# Power.net
KiCad netlist of a schematic drawn in Altium Designer
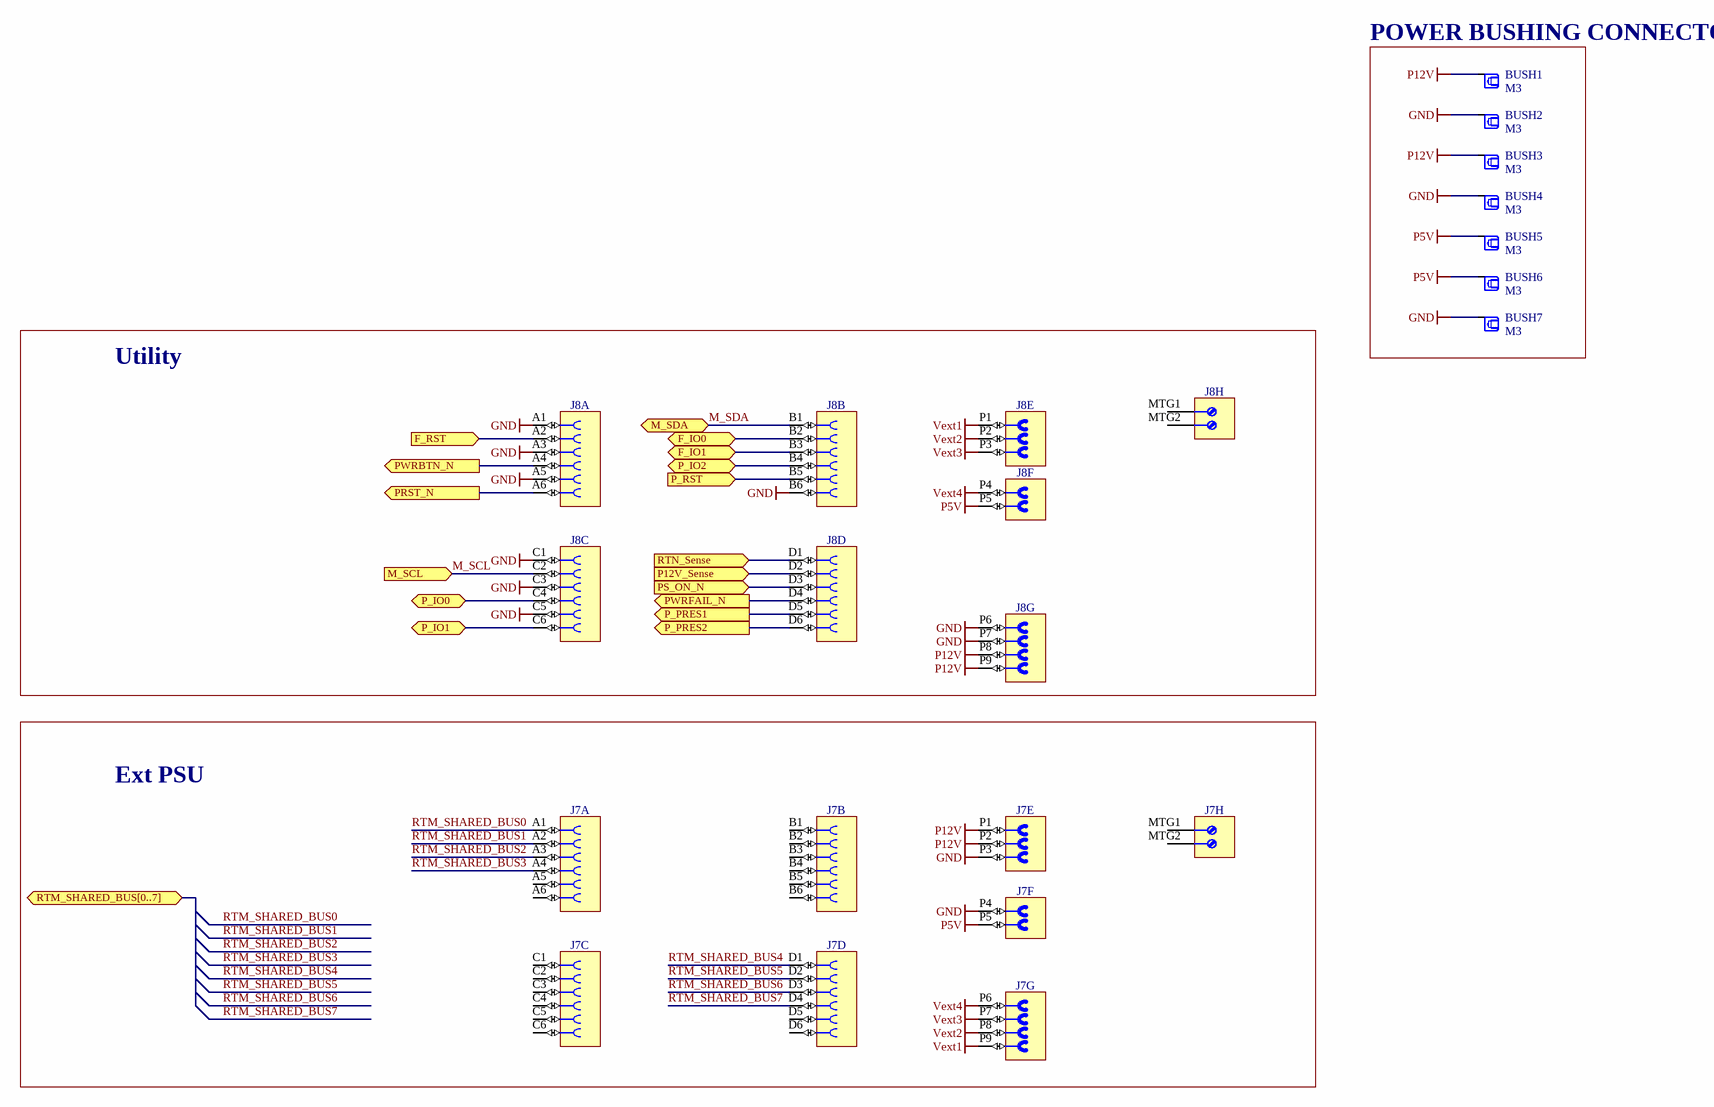
[diagram p0: Power.SchDoc]

(export (version "E")
  (design (tool "Eeschema 10.0.6"))
  (components
    (comp (ref "BUSH1")
      (value "M3")
      (footprint "WURTH_7461057")
      (description "Bush")
      (fields
        (field (name "PART NUMBER") "WURTH_7461057")
        (field (name "MANUFACTURER") "WURTH")
        (field (name "AUTHOR") "CERN DEM JLC")
      )
      (libsource (lib "Eletro-mechanical") (part "Bush"))
    )
    (comp (ref "BUSH2")
      (value "M3")
      (footprint "WURTH_7461057")
      (description "Bush")
      (fields
        (field (name "PART NUMBER") "WURTH_7461057")
        (field (name "MANUFACTURER") "WURTH")
        (field (name "AUTHOR") "CERN DEM JLC")
      )
      (libsource (lib "Eletro-mechanical") (part "Bush"))
    )
    (comp (ref "BUSH3")
      (value "M3")
      (footprint "WURTH_7461057")
      (description "Bush")
      (fields
        (field (name "PART NUMBER") "WURTH_7461057")
        (field (name "MANUFACTURER") "WURTH")
        (field (name "AUTHOR") "CERN DEM JLC")
      )
      (libsource (lib "Eletro-mechanical") (part "Bush"))
    )
    (comp (ref "BUSH4")
      (value "M3")
      (footprint "WURTH_7461057")
      (description "Bush")
      (fields
        (field (name "PART NUMBER") "WURTH_7461057")
        (field (name "MANUFACTURER") "WURTH")
        (field (name "AUTHOR") "CERN DEM JLC")
      )
      (libsource (lib "Eletro-mechanical") (part "Bush"))
    )
    (comp (ref "BUSH5")
      (value "M3")
      (footprint "WURTH_7461057")
      (description "Bush")
      (fields
        (field (name "PART NUMBER") "WURTH_7461057")
        (field (name "MANUFACTURER") "WURTH")
        (field (name "AUTHOR") "CERN DEM JLC")
      )
      (libsource (lib "Eletro-mechanical") (part "Bush"))
    )
    (comp (ref "BUSH6")
      (value "M3")
      (footprint "WURTH_7461057")
      (description "Bush")
      (fields
        (field (name "PART NUMBER") "WURTH_7461057")
        (field (name "MANUFACTURER") "WURTH")
        (field (name "AUTHOR") "CERN DEM JLC")
      )
      (libsource (lib "Eletro-mechanical") (part "Bush"))
    )
    (comp (ref "BUSH7")
      (value "M3")
      (footprint "WURTH_7461057")
      (description "Bush")
      (fields
        (field (name "PART NUMBER") "WURTH_7461057")
        (field (name "MANUFACTURER") "WURTH")
        (field (name "AUTHOR") "CERN DEM JLC")
      )
      (libsource (lib "Eletro-mechanical") (part "Bush"))
    )
    (comp (ref "J7")
      (value "PwrBlade")
      (footprint "AMPHENOL_51940-650")
      (description "Thru-Hole, Lead 3.43mm, PowerBlade Vertical Power Connector 3ACP 2P 24S 4DCP Contacts")
      (fields
        (field (name "PART NUMBER") "AMPHENOL_51940-650")
        (field (name "MANUFACTURER") "AMPHENOL")
        (field (name "AUTHOR") "CERN DEM HF")
      )
      (libsource (lib "Connectors") (part "AMPHENOL_51940-650"))
    )
    (comp (ref "J8")
      (value "PwrBlade")
      (footprint "AMPHENOL_51940-650")
      (description "Thru-Hole, Lead 3.43mm, PowerBlade Vertical Power Connector 3ACP 2P 24S 4DCP Contacts")
      (fields
        (field (name "PART NUMBER") "AMPHENOL_51940-650")
        (field (name "MANUFACTURER") "AMPHENOL")
        (field (name "AUTHOR") "CERN DEM HF")
      )
      (libsource (lib "Connectors") (part "AMPHENOL_51940-650"))
    )
  )
  (nets
    (net (code "1") (name "/F_IO0") (class "Default")
      (node (ref "J8") (pin "B2") (pinfunction "B2_B2") (pintype "bidirectional"))
    )
    (net (code "2") (name "/F_IO1") (class "Default")
      (node (ref "J8") (pin "B3") (pinfunction "B3_B3") (pintype "bidirectional"))
    )
    (net (code "3") (name "/F_RST") (class "Default")
      (node (ref "J8") (pin "A2") (pinfunction "A2_A2") (pintype "bidirectional"))
    )
    (net (code "4") (name "/M_SCL") (class "Default")
      (node (ref "J8") (pin "C2") (pinfunction "C2_C2") (pintype "bidirectional"))
    )
    (net (code "5") (name "/M_SDA") (class "Default")
      (node (ref "J8") (pin "B1") (pinfunction "B1_B1") (pintype "bidirectional"))
    )
    (net (code "6") (name "/P12V_Sense") (class "Default")
      (node (ref "J8") (pin "D2") (pinfunction "D2_D2") (pintype "bidirectional"))
    )
    (net (code "7") (name "/PRST_N") (class "Default")
      (node (ref "J8") (pin "A6") (pinfunction "A6_A6") (pintype "bidirectional"))
    )
    (net (code "8") (name "/PS_ON_N") (class "Default")
      (node (ref "J8") (pin "D3") (pinfunction "D3_D3") (pintype "bidirectional"))
    )
    (net (code "9") (name "/PWRBTN_N") (class "Default")
      (node (ref "J8") (pin "A4") (pinfunction "A4_A4") (pintype "bidirectional"))
    )
    (net (code "10") (name "/PWRFAIL_N") (class "Default")
      (node (ref "J8") (pin "D4") (pinfunction "D4_D4") (pintype "bidirectional"))
    )
    (net (code "11") (name "/P_IO0") (class "Default")
      (node (ref "J8") (pin "C4") (pinfunction "C4_C4") (pintype "bidirectional"))
    )
    (net (code "12") (name "/P_IO1") (class "Default")
      (node (ref "J8") (pin "C6") (pinfunction "C6_C6") (pintype "bidirectional"))
    )
    (net (code "13") (name "/P_IO2") (class "Default")
      (node (ref "J8") (pin "B4") (pinfunction "B4_B4") (pintype "bidirectional"))
    )
    (net (code "14") (name "/P_PRES1") (class "Default")
      (node (ref "J8") (pin "D5") (pinfunction "D5_D5") (pintype "bidirectional"))
    )
    (net (code "15") (name "/P_PRES2") (class "Default")
      (node (ref "J8") (pin "D6") (pinfunction "D6_D6") (pintype "bidirectional"))
    )
    (net (code "16") (name "/P_RST") (class "Default")
      (node (ref "J8") (pin "B5") (pinfunction "B5_B5") (pintype "bidirectional"))
    )
    (net (code "17") (name "/RTM_SHARED_BUS0") (class "Default")
      (node (ref "J7") (pin "A1") (pinfunction "A1_A1") (pintype "bidirectional"))
    )
    (net (code "18") (name "/RTM_SHARED_BUS1") (class "Default")
      (node (ref "J7") (pin "A2") (pinfunction "A2_A2") (pintype "bidirectional"))
    )
    (net (code "19") (name "/RTM_SHARED_BUS2") (class "Default")
      (node (ref "J7") (pin "A3") (pinfunction "A3_A3") (pintype "bidirectional"))
    )
    (net (code "20") (name "/RTM_SHARED_BUS3") (class "Default")
      (node (ref "J7") (pin "A4") (pinfunction "A4_A4") (pintype "bidirectional"))
    )
    (net (code "21") (name "/RTM_SHARED_BUS4") (class "Default")
      (node (ref "J7") (pin "D1") (pinfunction "D1_D1") (pintype "bidirectional"))
    )
    (net (code "22") (name "/RTM_SHARED_BUS5") (class "Default")
      (node (ref "J7") (pin "D2") (pinfunction "D2_D2") (pintype "bidirectional"))
    )
    (net (code "23") (name "/RTM_SHARED_BUS6") (class "Default")
      (node (ref "J7") (pin "D3") (pinfunction "D3_D3") (pintype "bidirectional"))
    )
    (net (code "24") (name "/RTM_SHARED_BUS7") (class "Default")
      (node (ref "J7") (pin "D4") (pinfunction "D4_D4") (pintype "bidirectional"))
    )
    (net (code "26") (name "/RTN_Sense") (class "Default")
      (node (ref "J8") (pin "D1") (pinfunction "D1_D1") (pintype "bidirectional"))
    )
    (net (code "27") (name "GND") (class "Default")
      (node (ref "BUSH2") (pin "1") (pinfunction "1_1") (pintype "bidirectional"))
      (node (ref "BUSH4") (pin "1") (pinfunction "1_1") (pintype "bidirectional"))
      (node (ref "BUSH7") (pin "1") (pinfunction "1_1") (pintype "bidirectional"))
      (node (ref "J7") (pin "P3") (pinfunction "P3_P3") (pintype "bidirectional"))
      (node (ref "J7") (pin "P4") (pinfunction "P4_P4") (pintype "bidirectional"))
      (node (ref "J8") (pin "A1") (pinfunction "A1_A1") (pintype "bidirectional"))
      (node (ref "J8") (pin "A3") (pinfunction "A3_A3") (pintype "bidirectional"))
      (node (ref "J8") (pin "A5") (pinfunction "A5_A5") (pintype "bidirectional"))
      (node (ref "J8") (pin "B6") (pinfunction "B6_B6") (pintype "bidirectional"))
      (node (ref "J8") (pin "C1") (pinfunction "C1_C1") (pintype "bidirectional"))
      (node (ref "J8") (pin "C3") (pinfunction "C3_C3") (pintype "bidirectional"))
      (node (ref "J8") (pin "C5") (pinfunction "C5_C5") (pintype "bidirectional"))
      (node (ref "J8") (pin "P6") (pinfunction "P6_P6") (pintype "bidirectional"))
      (node (ref "J8") (pin "P7") (pinfunction "P7_P7") (pintype "bidirectional"))
    )
    (net (code "28") (name "P5V") (class "Default")
      (node (ref "BUSH5") (pin "1") (pinfunction "1_1") (pintype "bidirectional"))
      (node (ref "BUSH6") (pin "1") (pinfunction "1_1") (pintype "bidirectional"))
      (node (ref "J7") (pin "P5") (pinfunction "P5_P5") (pintype "bidirectional"))
      (node (ref "J8") (pin "P5") (pinfunction "P5_P5") (pintype "bidirectional"))
    )
    (net (code "29") (name "P12V") (class "Default")
      (node (ref "BUSH1") (pin "1") (pinfunction "1_1") (pintype "bidirectional"))
      (node (ref "BUSH3") (pin "1") (pinfunction "1_1") (pintype "bidirectional"))
      (node (ref "J7") (pin "P1") (pinfunction "P1_P1") (pintype "bidirectional"))
      (node (ref "J7") (pin "P2") (pinfunction "P2_P2") (pintype "bidirectional"))
      (node (ref "J8") (pin "P8") (pinfunction "P8_P8") (pintype "bidirectional"))
      (node (ref "J8") (pin "P9") (pinfunction "P9_P9") (pintype "bidirectional"))
    )
    (net (code "30") (name "Vext1") (class "Default")
      (node (ref "J7") (pin "P9") (pinfunction "P9_P9") (pintype "bidirectional"))
      (node (ref "J8") (pin "P1") (pinfunction "P1_P1") (pintype "bidirectional"))
    )
    (net (code "31") (name "Vext2") (class "Default")
      (node (ref "J7") (pin "P8") (pinfunction "P8_P8") (pintype "bidirectional"))
      (node (ref "J8") (pin "P2") (pinfunction "P2_P2") (pintype "bidirectional"))
    )
    (net (code "32") (name "Vext3") (class "Default")
      (node (ref "J7") (pin "P7") (pinfunction "P7_P7") (pintype "bidirectional"))
      (node (ref "J8") (pin "P3") (pinfunction "P3_P3") (pintype "bidirectional"))
    )
    (net (code "33") (name "Vext4") (class "Default")
      (node (ref "J7") (pin "P6") (pinfunction "P6_P6") (pintype "bidirectional"))
      (node (ref "J8") (pin "P4") (pinfunction "P4_P4") (pintype "bidirectional"))
    )
    (net (code "34") (name "unconnected-(J7-PadA5)") (class "Default")
      (node (ref "J7") (pin "A5") (pinfunction "A5_A5") (pintype "bidirectional"))
    )
    (net (code "35") (name "unconnected-(J7-PadA6)") (class "Default")
      (node (ref "J7") (pin "A6") (pinfunction "A6_A6") (pintype "bidirectional"))
    )
    (net (code "36") (name "unconnected-(J7-PadB1)") (class "Default")
      (node (ref "J7") (pin "B1") (pinfunction "B1_B1") (pintype "bidirectional"))
    )
    (net (code "37") (name "unconnected-(J7-PadB2)") (class "Default")
      (node (ref "J7") (pin "B2") (pinfunction "B2_B2") (pintype "bidirectional"))
    )
    (net (code "38") (name "unconnected-(J7-PadB3)") (class "Default")
      (node (ref "J7") (pin "B3") (pinfunction "B3_B3") (pintype "bidirectional"))
    )
    (net (code "39") (name "unconnected-(J7-PadB4)") (class "Default")
      (node (ref "J7") (pin "B4") (pinfunction "B4_B4") (pintype "bidirectional"))
    )
    (net (code "40") (name "unconnected-(J7-PadB5)") (class "Default")
      (node (ref "J7") (pin "B5") (pinfunction "B5_B5") (pintype "bidirectional"))
    )
    (net (code "41") (name "unconnected-(J7-PadB6)") (class "Default")
      (node (ref "J7") (pin "B6") (pinfunction "B6_B6") (pintype "bidirectional"))
    )
    (net (code "42") (name "unconnected-(J7-PadC1)") (class "Default")
      (node (ref "J7") (pin "C1") (pinfunction "C1_C1") (pintype "bidirectional"))
    )
    (net (code "43") (name "unconnected-(J7-PadC2)") (class "Default")
      (node (ref "J7") (pin "C2") (pinfunction "C2_C2") (pintype "bidirectional"))
    )
    (net (code "44") (name "unconnected-(J7-PadC3)") (class "Default")
      (node (ref "J7") (pin "C3") (pinfunction "C3_C3") (pintype "bidirectional"))
    )
    (net (code "45") (name "unconnected-(J7-PadC4)") (class "Default")
      (node (ref "J7") (pin "C4") (pinfunction "C4_C4") (pintype "bidirectional"))
    )
    (net (code "46") (name "unconnected-(J7-PadC5)") (class "Default")
      (node (ref "J7") (pin "C5") (pinfunction "C5_C5") (pintype "bidirectional"))
    )
    (net (code "47") (name "unconnected-(J7-PadC6)") (class "Default")
      (node (ref "J7") (pin "C6") (pinfunction "C6_C6") (pintype "bidirectional"))
    )
    (net (code "48") (name "unconnected-(J7-PadD5)") (class "Default")
      (node (ref "J7") (pin "D5") (pinfunction "D5_D5") (pintype "bidirectional"))
    )
    (net (code "49") (name "unconnected-(J7-PadD6)") (class "Default")
      (node (ref "J7") (pin "D6") (pinfunction "D6_D6") (pintype "bidirectional"))
    )
    (net (code "50") (name "unconnected-(J7-PadMTG1)") (class "Default")
      (node (ref "J7") (pin "MTG1") (pinfunction "MTG1_MTG1") (pintype "passive"))
    )
    (net (code "51") (name "unconnected-(J7-PadMTG2)") (class "Default")
      (node (ref "J7") (pin "MTG2") (pinfunction "MTG2_MTG2") (pintype "passive"))
    )
    (net (code "52") (name "unconnected-(J8-PadMTG1)") (class "Default")
      (node (ref "J8") (pin "MTG1") (pinfunction "MTG1_MTG1") (pintype "passive"))
    )
    (net (code "53") (name "unconnected-(J8-PadMTG2)") (class "Default")
      (node (ref "J8") (pin "MTG2") (pinfunction "MTG2_MTG2") (pintype "passive"))
    )
  )
)
